# CrackberryPi_1_0_6_2_random2.net
KiCad netlist of a schematic drawn in EAGLE
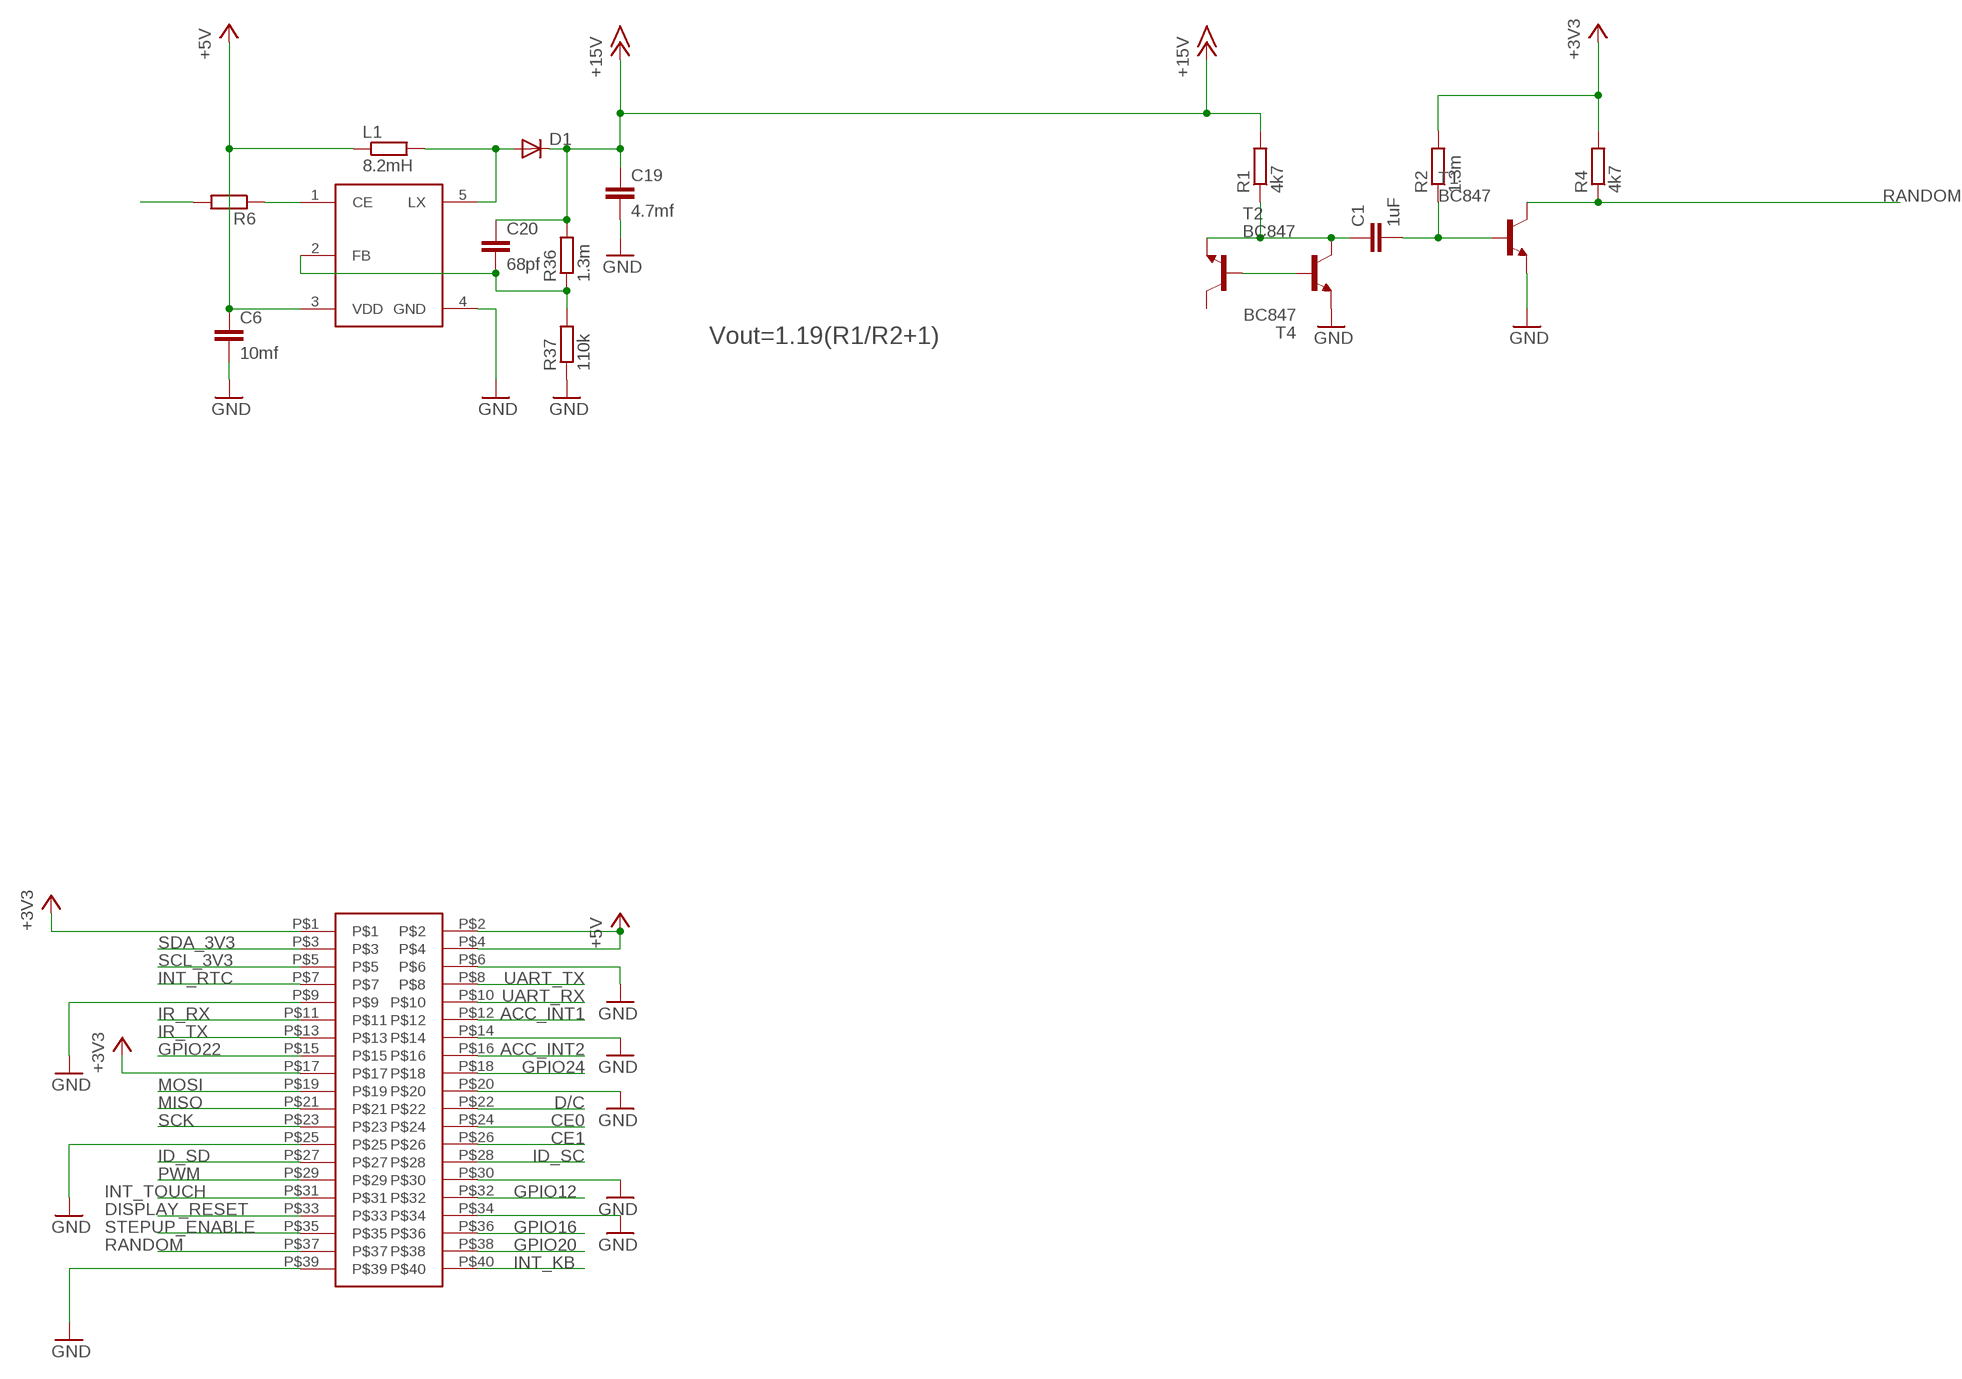
[diagram p0: schematic, sheet 1]

(export (version "E")
  (design (tool "Eeschema 10.0.6"))
  (components
    (comp (ref "C1")
      (value "1uF")
      (footprint "eagle-import:C0603")
      (libsource (lib "eagle-import") (part "C-EUC0603"))
    )
    (comp (ref "C6")
      (value "10mf")
      (footprint "eagle-import:C0603")
      (libsource (lib "eagle-import") (part "C-EUC0603"))
    )
    (comp (ref "C19")
      (value "4.7mf")
      (footprint "eagle-import:C0603")
      (libsource (lib "eagle-import") (part "C-EUC0603"))
    )
    (comp (ref "C20")
      (value "68pf")
      (footprint "eagle-import:C0603")
      (libsource (lib "eagle-import") (part "C-EUC0603"))
    )
    (comp (ref "D1")
      (value "DIODE-SOD123")
      (footprint "eagle-import:SOD123")
      (libsource (lib "eagle-import") (part "DIODE-SOD123"))
    )
    (comp (ref "L1")
      (value "8.2mH")
      (footprint "eagle-import:R1210")
      (libsource (lib "eagle-import") (part "R-EU_R1210"))
    )
    (comp (ref "R1")
      (value "4k7")
      (footprint "eagle-import:R0603")
      (libsource (lib "eagle-import") (part "R-EU_R0603"))
    )
    (comp (ref "R2")
      (value "1.3m")
      (footprint "eagle-import:R0603")
      (libsource (lib "eagle-import") (part "R-EU_R0603"))
    )
    (comp (ref "R4")
      (value "4k7")
      (footprint "eagle-import:R0603")
      (libsource (lib "eagle-import") (part "R-EU_R0603"))
    )
    (comp (ref "R6")
      (value "R-EU_R1210")
      (footprint "eagle-import:R1210")
      (libsource (lib "eagle-import") (part "R-EU_R1210"))
    )
    (comp (ref "R36")
      (value "1.3m")
      (footprint "eagle-import:R0603")
      (libsource (lib "eagle-import") (part "R-EU_R0603"))
    )
    (comp (ref "R37")
      (value "110k")
      (footprint "eagle-import:R0603")
      (libsource (lib "eagle-import") (part "R-EU_R0603"))
    )
    (comp (ref "T1")
      (value "BC847")
      (footprint "eagle-import:SOT23")
      (libsource (lib "eagle-import") (part "BC847"))
    )
    (comp (ref "T2")
      (value "BC847")
      (footprint "eagle-import:SOT23")
      (libsource (lib "eagle-import") (part "BC847"))
    )
    (comp (ref "T4")
      (value "BC847")
      (footprint "eagle-import:SOT23")
      (libsource (lib "eagle-import") (part "BC847"))
    )
    (comp (ref "U$2")
      (value "NCP1406")
      (footprint "eagle-import:SOT23-5L")
      (libsource (lib "eagle-import") (part "NCP1406"))
    )
    (comp (ref "U$11")
      (value "HEADER")
      (footprint "eagle-import:20X2")
      (libsource (lib "eagle-import") (part "HEADER"))
    )
  )
  (nets
    (net (code "1") (name "+3V3") (class "Default")
      (node (ref "R2") (pin "2") (pinfunction "2_2") (pintype "passive"))
      (node (ref "R4") (pin "2") (pinfunction "2_2") (pintype "passive"))
      (node (ref "U$11") (pin "P$1") (pinfunction "P$1_P$1") (pintype "bidirectional"))
      (node (ref "U$11") (pin "P$17") (pinfunction "P$17_P$17") (pintype "bidirectional"))
    )
    (net (code "2") (name "+5V") (class "Default")
      (node (ref "C6") (pin "1") (pinfunction "1_1") (pintype "passive"))
      (node (ref "L1") (pin "1") (pinfunction "1_1") (pintype "passive"))
      (node (ref "U$11") (pin "P$2") (pinfunction "P$2_P$2") (pintype "bidirectional"))
      (node (ref "U$11") (pin "P$4") (pinfunction "P$4_P$4") (pintype "bidirectional"))
      (node (ref "U$2") (pin "3") (pinfunction "VDD_3") (pintype "bidirectional"))
    )
    (net (code "3") (name "+15V") (class "Default")
      (node (ref "C19") (pin "1") (pinfunction "1_1") (pintype "passive"))
      (node (ref "C20") (pin "1") (pinfunction "1_1") (pintype "passive"))
      (node (ref "D1") (pin "C") (pinfunction "C_C") (pintype "passive"))
      (node (ref "R1") (pin "2") (pinfunction "2_2") (pintype "passive"))
      (node (ref "R36") (pin "2") (pinfunction "2_2") (pintype "passive"))
    )
    (net (code "4") (name "/ACC_INT1") (class "Default")
      (node (ref "U$11") (pin "P$12") (pinfunction "P$12_P$12") (pintype "bidirectional"))
    )
    (net (code "5") (name "/ACC_INT2") (class "Default")
      (node (ref "U$11") (pin "P$16") (pinfunction "P$16_P$16") (pintype "bidirectional"))
    )
    (net (code "6") (name "/CE0") (class "Default")
      (node (ref "U$11") (pin "P$24") (pinfunction "P$24_P$24") (pintype "bidirectional"))
    )
    (net (code "7") (name "/CE1") (class "Default")
      (node (ref "U$11") (pin "P$26") (pinfunction "P$26_P$26") (pintype "bidirectional"))
    )
    (net (code "8") (name "/DISPLAY_RESET") (class "Default")
      (node (ref "U$11") (pin "P$33") (pinfunction "P$33_P$33") (pintype "bidirectional"))
    )
    (net (code "9") (name "/D{slash}C") (class "Default")
      (node (ref "U$11") (pin "P$22") (pinfunction "P$22_P$22") (pintype "bidirectional"))
    )
    (net (code "10") (name "/GPIO12") (class "Default")
      (node (ref "U$11") (pin "P$32") (pinfunction "P$32_P$32") (pintype "bidirectional"))
    )
    (net (code "11") (name "/GPIO16") (class "Default")
      (node (ref "U$11") (pin "P$36") (pinfunction "P$36_P$36") (pintype "bidirectional"))
    )
    (net (code "12") (name "/GPIO20") (class "Default")
      (node (ref "U$11") (pin "P$38") (pinfunction "P$38_P$38") (pintype "bidirectional"))
    )
    (net (code "13") (name "/GPIO22") (class "Default")
      (node (ref "U$11") (pin "P$15") (pinfunction "P$15_P$15") (pintype "bidirectional"))
    )
    (net (code "14") (name "/GPIO24") (class "Default")
      (node (ref "U$11") (pin "P$18") (pinfunction "P$18_P$18") (pintype "bidirectional"))
    )
    (net (code "15") (name "/ID_SC") (class "Default")
      (node (ref "U$11") (pin "P$28") (pinfunction "P$28_P$28") (pintype "bidirectional"))
    )
    (net (code "16") (name "/ID_SD") (class "Default")
      (node (ref "U$11") (pin "P$27") (pinfunction "P$27_P$27") (pintype "bidirectional"))
    )
    (net (code "17") (name "/INT_KB") (class "Default")
      (node (ref "U$11") (pin "P$40") (pinfunction "P$40_P$40") (pintype "bidirectional"))
    )
    (net (code "18") (name "/INT_RTC") (class "Default")
      (node (ref "U$11") (pin "P$7") (pinfunction "P$7_P$7") (pintype "bidirectional"))
    )
    (net (code "19") (name "/INT_TOUCH") (class "Default")
      (node (ref "U$11") (pin "P$31") (pinfunction "P$31_P$31") (pintype "bidirectional"))
    )
    (net (code "20") (name "/IR_RX") (class "Default")
      (node (ref "U$11") (pin "P$11") (pinfunction "P$11_P$11") (pintype "bidirectional"))
    )
    (net (code "21") (name "/IR_TX") (class "Default")
      (node (ref "U$11") (pin "P$13") (pinfunction "P$13_P$13") (pintype "bidirectional"))
    )
    (net (code "22") (name "/MISO") (class "Default")
      (node (ref "U$11") (pin "P$21") (pinfunction "P$21_P$21") (pintype "bidirectional"))
    )
    (net (code "23") (name "/MOSI") (class "Default")
      (node (ref "U$11") (pin "P$19") (pinfunction "P$19_P$19") (pintype "bidirectional"))
    )
    (net (code "24") (name "/PWM") (class "Default")
      (node (ref "U$11") (pin "P$29") (pinfunction "P$29_P$29") (pintype "bidirectional"))
    )
    (net (code "25") (name "/RANDOM") (class "Default")
      (node (ref "R4") (pin "1") (pinfunction "1_1") (pintype "passive"))
      (node (ref "T1") (pin "3") (pinfunction "C_3") (pintype "passive"))
      (node (ref "U$11") (pin "P$37") (pinfunction "P$37_P$37") (pintype "bidirectional"))
    )
    (net (code "26") (name "/SCK") (class "Default")
      (node (ref "U$11") (pin "P$23") (pinfunction "P$23_P$23") (pintype "bidirectional"))
    )
    (net (code "27") (name "/SCL_3V3") (class "Default")
      (node (ref "U$11") (pin "P$5") (pinfunction "P$5_P$5") (pintype "bidirectional"))
    )
    (net (code "28") (name "/SDA_3V3") (class "Default")
      (node (ref "U$11") (pin "P$3") (pinfunction "P$3_P$3") (pintype "bidirectional"))
    )
    (net (code "29") (name "/STEPUP_ENABLE") (class "Default")
      (node (ref "R6") (pin "2") (pinfunction "2_2") (pintype "passive"))
      (node (ref "U$11") (pin "P$35") (pinfunction "P$35_P$35") (pintype "bidirectional"))
    )
    (net (code "30") (name "/UART_RX") (class "Default")
      (node (ref "U$11") (pin "P$10") (pinfunction "P$10_P$10") (pintype "bidirectional"))
    )
    (net (code "31") (name "/UART_TX") (class "Default")
      (node (ref "U$11") (pin "P$8") (pinfunction "P$8_P$8") (pintype "bidirectional"))
    )
    (net (code "32") (name "GND") (class "Default")
      (node (ref "C19") (pin "2") (pinfunction "2_2") (pintype "passive"))
      (node (ref "C6") (pin "2") (pinfunction "2_2") (pintype "passive"))
      (node (ref "R37") (pin "1") (pinfunction "1_1") (pintype "passive"))
      (node (ref "T1") (pin "2") (pinfunction "E_2") (pintype "passive"))
      (node (ref "T2") (pin "2") (pinfunction "E_2") (pintype "passive"))
      (node (ref "U$11") (pin "P$14") (pinfunction "P$14_P$14") (pintype "bidirectional"))
      (node (ref "U$11") (pin "P$20") (pinfunction "P$20_P$20") (pintype "bidirectional"))
      (node (ref "U$11") (pin "P$25") (pinfunction "P$25_P$25") (pintype "bidirectional"))
      (node (ref "U$11") (pin "P$30") (pinfunction "P$30_P$30") (pintype "bidirectional"))
      (node (ref "U$11") (pin "P$34") (pinfunction "P$34_P$34") (pintype "bidirectional"))
      (node (ref "U$11") (pin "P$39") (pinfunction "P$39_P$39") (pintype "bidirectional"))
      (node (ref "U$11") (pin "P$6") (pinfunction "P$6_P$6") (pintype "bidirectional"))
      (node (ref "U$11") (pin "P$9") (pinfunction "P$9_P$9") (pintype "bidirectional"))
      (node (ref "U$2") (pin "4") (pinfunction "GND_4") (pintype "bidirectional"))
    )
    (net (code "33") (name "Net-(T1-B)") (class "Default")
      (node (ref "C1") (pin "2") (pinfunction "2_2") (pintype "passive"))
      (node (ref "R2") (pin "1") (pinfunction "1_1") (pintype "passive"))
      (node (ref "T1") (pin "1") (pinfunction "B_1") (pintype "passive"))
    )
    (net (code "34") (name "Net-(T2-B)") (class "Default")
      (node (ref "T2") (pin "1") (pinfunction "B_1") (pintype "passive"))
      (node (ref "T4") (pin "1") (pinfunction "B_1") (pintype "passive"))
    )
    (net (code "35") (name "Net-(T2-C)") (class "Default")
      (node (ref "C1") (pin "1") (pinfunction "1_1") (pintype "passive"))
      (node (ref "R1") (pin "1") (pinfunction "1_1") (pintype "passive"))
      (node (ref "T2") (pin "3") (pinfunction "C_3") (pintype "passive"))
      (node (ref "T4") (pin "2") (pinfunction "E_2") (pintype "passive"))
    )
    (net (code "36") (name "Net-(U$2-CE)") (class "Default")
      (node (ref "R6") (pin "1") (pinfunction "1_1") (pintype "passive"))
      (node (ref "U$2") (pin "1") (pinfunction "CE_1") (pintype "bidirectional"))
    )
    (net (code "37") (name "Net-(U$2-FB)") (class "Default")
      (node (ref "C20") (pin "2") (pinfunction "2_2") (pintype "passive"))
      (node (ref "R36") (pin "1") (pinfunction "1_1") (pintype "passive"))
      (node (ref "R37") (pin "2") (pinfunction "2_2") (pintype "passive"))
      (node (ref "U$2") (pin "2") (pinfunction "FB_2") (pintype "bidirectional"))
    )
    (net (code "38") (name "Net-(U$2-LX)") (class "Default")
      (node (ref "D1") (pin "A") (pinfunction "A_A") (pintype "passive"))
      (node (ref "L1") (pin "2") (pinfunction "2_2") (pintype "passive"))
      (node (ref "U$2") (pin "5") (pinfunction "LX_5") (pintype "bidirectional"))
    )
    (net (code "39") (name "unconnected-(T4-C-Pad3)") (class "Default")
      (node (ref "T4") (pin "3") (pinfunction "C_3") (pintype "passive"))
    )
  )
)
